# D_OUTPUT.net
KiCad netlist of a schematic drawn in Altium Designer
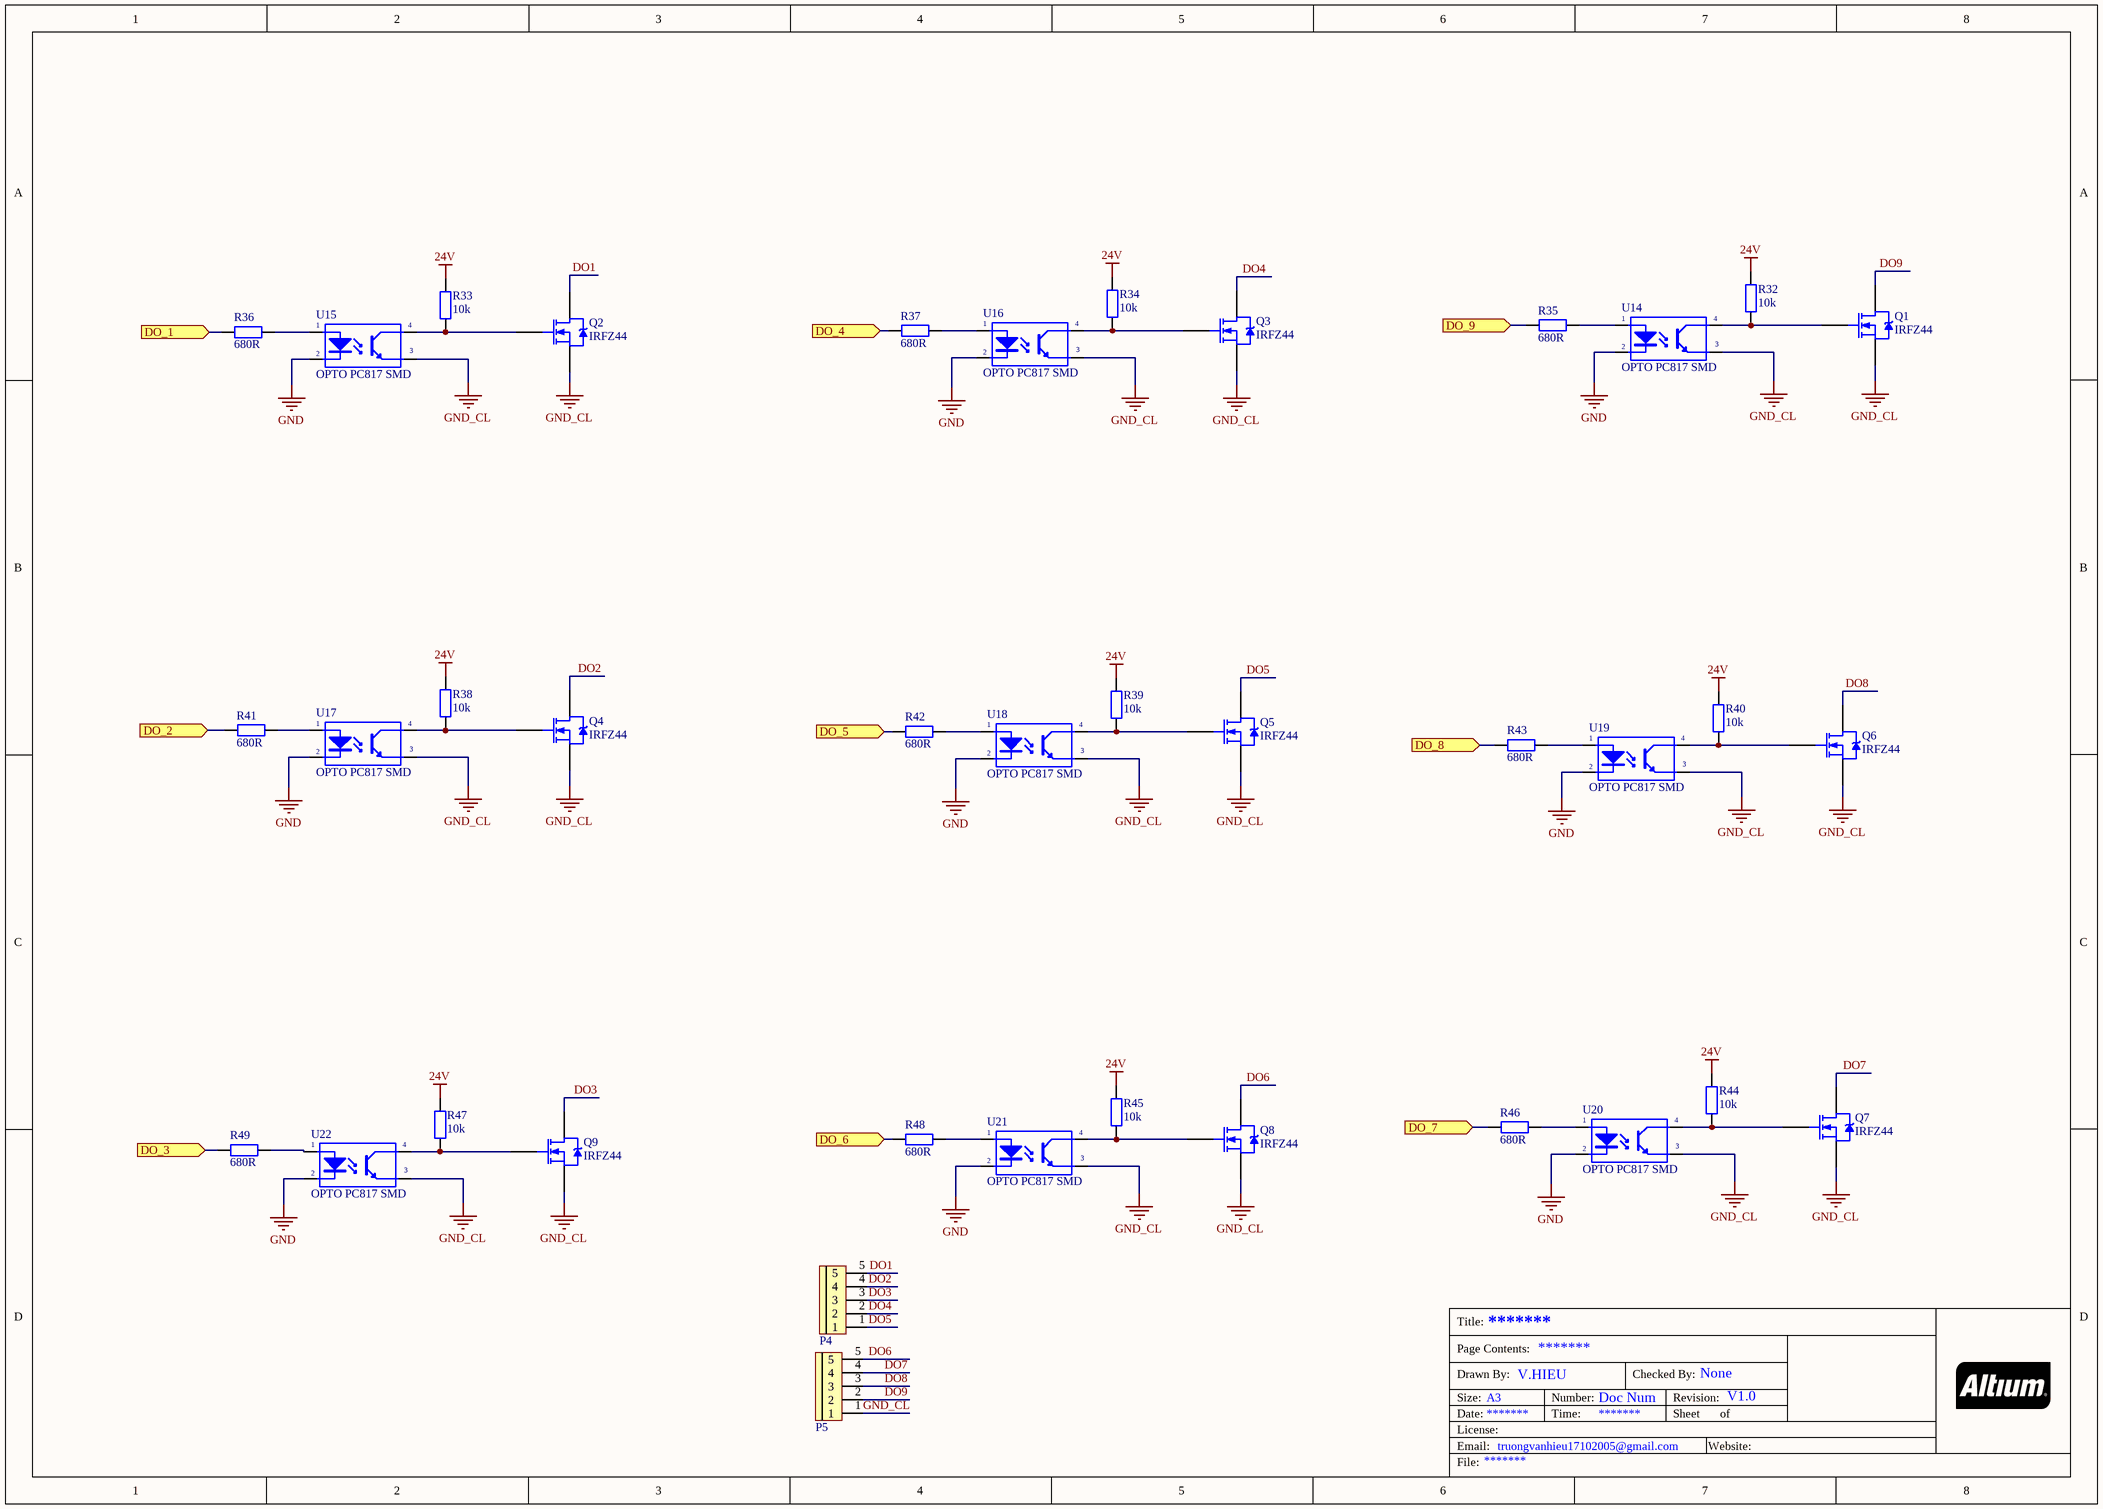
[diagram p0: D_OUTPUT.SchDoc]

(export (version "E")
  (design (tool "Eeschema 10.0.6"))
  (components
    (comp (ref "P4")
      (value "CON 5 EDG5.08")
      (footprint "CON 5 5EDG5.08")
      (description "Cắm")
      (libsource (lib "Altium_Lib_by_KhueNguyenCreator") (part "CON 5 EDG5.08"))
    )
    (comp (ref "P5")
      (value "CON 5 EDG5.08")
      (footprint "CON 5 5EDG5.08")
      (description "Cắm")
      (libsource (lib "Altium_Lib_by_KhueNguyenCreator") (part "CON 5 EDG5.08"))
    )
    (comp (ref "Q1")
      (value "IRFZ44")
      (footprint "TO220")
      (description "TO-220")
      (libsource (lib "Altium_Lib_by_KhueNguyenCreator") (part "FET IRFZ44 DIP"))
    )
    (comp (ref "Q2")
      (value "IRFZ44")
      (footprint "TO220")
      (description "TO-220")
      (libsource (lib "Altium_Lib_by_KhueNguyenCreator") (part "FET IRFZ44 DIP"))
    )
    (comp (ref "Q3")
      (value "IRFZ44")
      (footprint "TO220")
      (description "TO-220")
      (libsource (lib "Altium_Lib_by_KhueNguyenCreator") (part "FET IRFZ44 DIP"))
    )
    (comp (ref "Q4")
      (value "IRFZ44")
      (footprint "TO220")
      (description "TO-220")
      (libsource (lib "Altium_Lib_by_KhueNguyenCreator") (part "FET IRFZ44 DIP"))
    )
    (comp (ref "Q5")
      (value "IRFZ44")
      (footprint "TO220")
      (description "TO-220")
      (libsource (lib "Altium_Lib_by_KhueNguyenCreator") (part "FET IRFZ44 DIP"))
    )
    (comp (ref "Q6")
      (value "IRFZ44")
      (footprint "TO220")
      (description "TO-220")
      (libsource (lib "Altium_Lib_by_KhueNguyenCreator") (part "FET IRFZ44 DIP"))
    )
    (comp (ref "Q7")
      (value "IRFZ44")
      (footprint "TO220")
      (description "TO-220")
      (libsource (lib "Altium_Lib_by_KhueNguyenCreator") (part "FET IRFZ44 DIP"))
    )
    (comp (ref "Q8")
      (value "IRFZ44")
      (footprint "TO220")
      (description "TO-220")
      (libsource (lib "Altium_Lib_by_KhueNguyenCreator") (part "FET IRFZ44 DIP"))
    )
    (comp (ref "Q9")
      (value "IRFZ44")
      (footprint "TO220")
      (description "TO-220")
      (libsource (lib "Altium_Lib_by_KhueNguyenCreator") (part "FET IRFZ44 DIP"))
    )
    (comp (ref "R32")
      (value "10k")
      (footprint "tro smd 0805")
      (description "Dán")
      (libsource (lib "Altium_Lib_by_KhueNguyenCreator") (part "Tro 0805 1% 10k"))
    )
    (comp (ref "R33")
      (value "10k")
      (footprint "tro smd 0805")
      (description "Dán")
      (libsource (lib "Altium_Lib_by_KhueNguyenCreator") (part "Tro 0805 1% 10k"))
    )
    (comp (ref "R34")
      (value "10k")
      (footprint "tro smd 0805")
      (description "Dán")
      (libsource (lib "Altium_Lib_by_KhueNguyenCreator") (part "Tro 0805 1% 10k"))
    )
    (comp (ref "R35")
      (value "680R")
      (footprint "Tro SMD 0805")
      (description "Dán")
      (libsource (lib "Altium_Lib_by_KhueNguyenCreator") (part "Tro 0805 5% 680R"))
    )
    (comp (ref "R36")
      (value "680R")
      (footprint "Tro SMD 0805")
      (description "Dán")
      (libsource (lib "Altium_Lib_by_KhueNguyenCreator") (part "Tro 0805 5% 680R"))
    )
    (comp (ref "R37")
      (value "680R")
      (footprint "Tro SMD 0805")
      (description "Dán")
      (libsource (lib "Altium_Lib_by_KhueNguyenCreator") (part "Tro 0805 5% 680R"))
    )
    (comp (ref "R38")
      (value "10k")
      (footprint "tro smd 0805")
      (description "Dán")
      (libsource (lib "Altium_Lib_by_KhueNguyenCreator") (part "Tro 0805 1% 10k"))
    )
    (comp (ref "R39")
      (value "10k")
      (footprint "tro smd 0805")
      (description "Dán")
      (libsource (lib "Altium_Lib_by_KhueNguyenCreator") (part "Tro 0805 1% 10k"))
    )
    (comp (ref "R40")
      (value "10k")
      (footprint "tro smd 0805")
      (description "Dán")
      (libsource (lib "Altium_Lib_by_KhueNguyenCreator") (part "Tro 0805 1% 10k"))
    )
    (comp (ref "R41")
      (value "680R")
      (footprint "Tro SMD 0805")
      (description "Dán")
      (libsource (lib "Altium_Lib_by_KhueNguyenCreator") (part "Tro 0805 5% 680R"))
    )
    (comp (ref "R42")
      (value "680R")
      (footprint "Tro SMD 0805")
      (description "Dán")
      (libsource (lib "Altium_Lib_by_KhueNguyenCreator") (part "Tro 0805 5% 680R"))
    )
    (comp (ref "R43")
      (value "680R")
      (footprint "Tro SMD 0805")
      (description "Dán")
      (libsource (lib "Altium_Lib_by_KhueNguyenCreator") (part "Tro 0805 5% 680R"))
    )
    (comp (ref "R44")
      (value "10k")
      (footprint "tro smd 0805")
      (description "Dán")
      (libsource (lib "Altium_Lib_by_KhueNguyenCreator") (part "Tro 0805 1% 10k"))
    )
    (comp (ref "R45")
      (value "10k")
      (footprint "tro smd 0805")
      (description "Dán")
      (libsource (lib "Altium_Lib_by_KhueNguyenCreator") (part "Tro 0805 1% 10k"))
    )
    (comp (ref "R46")
      (value "680R")
      (footprint "Tro SMD 0805")
      (description "Dán")
      (libsource (lib "Altium_Lib_by_KhueNguyenCreator") (part "Tro 0805 5% 680R"))
    )
    (comp (ref "R47")
      (value "10k")
      (footprint "tro smd 0805")
      (description "Dán")
      (libsource (lib "Altium_Lib_by_KhueNguyenCreator") (part "Tro 0805 1% 10k"))
    )
    (comp (ref "R48")
      (value "680R")
      (footprint "Tro SMD 0805")
      (description "Dán")
      (libsource (lib "Altium_Lib_by_KhueNguyenCreator") (part "Tro 0805 5% 680R"))
    )
    (comp (ref "R49")
      (value "680R")
      (footprint "Tro SMD 0805")
      (description "Dán")
      (libsource (lib "Altium_Lib_by_KhueNguyenCreator") (part "Tro 0805 5% 680R"))
    )
    (comp (ref "U14")
      (value "OPTO PC817 SMD")
      (footprint "SOP4")
      (description "Single Opto")
      (libsource (lib "Altium_Lib_by_KhueNguyenCreator") (part "OPTO PC817 SMD"))
    )
    (comp (ref "U15")
      (value "OPTO PC817 SMD")
      (footprint "SOP4")
      (description "Single Opto")
      (libsource (lib "Altium_Lib_by_KhueNguyenCreator") (part "OPTO PC817 SMD"))
    )
    (comp (ref "U16")
      (value "OPTO PC817 SMD")
      (footprint "SOP4")
      (description "Single Opto")
      (libsource (lib "Altium_Lib_by_KhueNguyenCreator") (part "OPTO PC817 SMD"))
    )
    (comp (ref "U17")
      (value "OPTO PC817 SMD")
      (footprint "SOP4")
      (description "Single Opto")
      (libsource (lib "Altium_Lib_by_KhueNguyenCreator") (part "OPTO PC817 SMD"))
    )
    (comp (ref "U18")
      (value "OPTO PC817 SMD")
      (footprint "SOP4")
      (description "Single Opto")
      (libsource (lib "Altium_Lib_by_KhueNguyenCreator") (part "OPTO PC817 SMD"))
    )
    (comp (ref "U19")
      (value "OPTO PC817 SMD")
      (footprint "SOP4")
      (description "Single Opto")
      (libsource (lib "Altium_Lib_by_KhueNguyenCreator") (part "OPTO PC817 SMD"))
    )
    (comp (ref "U20")
      (value "OPTO PC817 SMD")
      (footprint "SOP4")
      (description "Single Opto")
      (libsource (lib "Altium_Lib_by_KhueNguyenCreator") (part "OPTO PC817 SMD"))
    )
    (comp (ref "U21")
      (value "OPTO PC817 SMD")
      (footprint "SOP4")
      (description "Single Opto")
      (libsource (lib "Altium_Lib_by_KhueNguyenCreator") (part "OPTO PC817 SMD"))
    )
    (comp (ref "U22")
      (value "OPTO PC817 SMD")
      (footprint "SOP4")
      (description "Single Opto")
      (libsource (lib "Altium_Lib_by_KhueNguyenCreator") (part "OPTO PC817 SMD"))
    )
  )
  (nets
    (net (code "1") (name "/DO1") (class "Default")
      (node (ref "P4") (pin "5") (pinfunction "5_5") (pintype "passive"))
      (node (ref "Q2") (pin "2") (pinfunction "D_2") (pintype "passive"))
    )
    (net (code "2") (name "/DO2") (class "Default")
      (node (ref "P4") (pin "4") (pinfunction "4_4") (pintype "passive"))
      (node (ref "Q4") (pin "2") (pinfunction "D_2") (pintype "passive"))
    )
    (net (code "3") (name "/DO3") (class "Default")
      (node (ref "P4") (pin "3") (pinfunction "3_3") (pintype "passive"))
      (node (ref "Q9") (pin "2") (pinfunction "D_2") (pintype "passive"))
    )
    (net (code "4") (name "/DO4") (class "Default")
      (node (ref "P4") (pin "2") (pinfunction "2_2") (pintype "passive"))
      (node (ref "Q3") (pin "2") (pinfunction "D_2") (pintype "passive"))
    )
    (net (code "5") (name "/DO5") (class "Default")
      (node (ref "P4") (pin "1") (pinfunction "1_1") (pintype "passive"))
      (node (ref "Q5") (pin "2") (pinfunction "D_2") (pintype "passive"))
    )
    (net (code "6") (name "/DO6") (class "Default")
      (node (ref "P5") (pin "5") (pinfunction "5_5") (pintype "passive"))
      (node (ref "Q8") (pin "2") (pinfunction "D_2") (pintype "passive"))
    )
    (net (code "7") (name "/DO7") (class "Default")
      (node (ref "P5") (pin "4") (pinfunction "4_4") (pintype "passive"))
      (node (ref "Q7") (pin "2") (pinfunction "D_2") (pintype "passive"))
    )
    (net (code "8") (name "/DO8") (class "Default")
      (node (ref "P5") (pin "3") (pinfunction "3_3") (pintype "passive"))
      (node (ref "Q6") (pin "2") (pinfunction "D_2") (pintype "passive"))
    )
    (net (code "9") (name "/DO9") (class "Default")
      (node (ref "P5") (pin "2") (pinfunction "2_2") (pintype "passive"))
      (node (ref "Q1") (pin "2") (pinfunction "D_2") (pintype "passive"))
    )
    (net (code "10") (name "/DO_1") (class "Default")
      (node (ref "R36") (pin "1") (pinfunction "1_1") (pintype "passive"))
    )
    (net (code "11") (name "/DO_2") (class "Default")
      (node (ref "R41") (pin "1") (pinfunction "1_1") (pintype "passive"))
    )
    (net (code "12") (name "/DO_3") (class "Default")
      (node (ref "R49") (pin "1") (pinfunction "1_1") (pintype "passive"))
    )
    (net (code "13") (name "/DO_4") (class "Default")
      (node (ref "R37") (pin "1") (pinfunction "1_1") (pintype "passive"))
    )
    (net (code "14") (name "/DO_5") (class "Default")
      (node (ref "R42") (pin "1") (pinfunction "1_1") (pintype "passive"))
    )
    (net (code "15") (name "/DO_6") (class "Default")
      (node (ref "R48") (pin "1") (pinfunction "1_1") (pintype "passive"))
    )
    (net (code "16") (name "/DO_7") (class "Default")
      (node (ref "R46") (pin "1") (pinfunction "1_1") (pintype "passive"))
    )
    (net (code "17") (name "/DO_8") (class "Default")
      (node (ref "R43") (pin "1") (pinfunction "1_1") (pintype "passive"))
    )
    (net (code "18") (name "/DO_9") (class "Default")
      (node (ref "R35") (pin "1") (pinfunction "1_1") (pintype "passive"))
    )
    (net (code "19") (name "24V") (class "Default")
      (node (ref "R32") (pin "1") (pinfunction "1_1") (pintype "passive"))
      (node (ref "R33") (pin "1") (pinfunction "1_1") (pintype "passive"))
      (node (ref "R34") (pin "1") (pinfunction "1_1") (pintype "passive"))
      (node (ref "R38") (pin "1") (pinfunction "1_1") (pintype "passive"))
      (node (ref "R39") (pin "1") (pinfunction "1_1") (pintype "passive"))
      (node (ref "R40") (pin "1") (pinfunction "1_1") (pintype "passive"))
      (node (ref "R44") (pin "1") (pinfunction "1_1") (pintype "passive"))
      (node (ref "R45") (pin "1") (pinfunction "1_1") (pintype "passive"))
      (node (ref "R47") (pin "1") (pinfunction "1_1") (pintype "passive"))
    )
    (net (code "20") (name "GND") (class "Default")
      (node (ref "U14") (pin "2") (pinfunction "K_2") (pintype "passive"))
      (node (ref "U15") (pin "2") (pinfunction "K_2") (pintype "passive"))
      (node (ref "U16") (pin "2") (pinfunction "K_2") (pintype "passive"))
      (node (ref "U17") (pin "2") (pinfunction "K_2") (pintype "passive"))
      (node (ref "U18") (pin "2") (pinfunction "K_2") (pintype "passive"))
      (node (ref "U19") (pin "2") (pinfunction "K_2") (pintype "passive"))
      (node (ref "U20") (pin "2") (pinfunction "K_2") (pintype "passive"))
      (node (ref "U21") (pin "2") (pinfunction "K_2") (pintype "passive"))
      (node (ref "U22") (pin "2") (pinfunction "K_2") (pintype "passive"))
    )
    (net (code "21") (name "GND_CL") (class "Default")
      (node (ref "P5") (pin "1") (pinfunction "1_1") (pintype "passive"))
      (node (ref "Q1") (pin "3") (pinfunction "S_3") (pintype "passive"))
      (node (ref "Q2") (pin "3") (pinfunction "S_3") (pintype "passive"))
      (node (ref "Q3") (pin "3") (pinfunction "S_3") (pintype "passive"))
      (node (ref "Q4") (pin "3") (pinfunction "S_3") (pintype "passive"))
      (node (ref "Q5") (pin "3") (pinfunction "S_3") (pintype "passive"))
      (node (ref "Q6") (pin "3") (pinfunction "S_3") (pintype "passive"))
      (node (ref "Q7") (pin "3") (pinfunction "S_3") (pintype "passive"))
      (node (ref "Q8") (pin "3") (pinfunction "S_3") (pintype "passive"))
      (node (ref "Q9") (pin "3") (pinfunction "S_3") (pintype "passive"))
      (node (ref "U14") (pin "3") (pinfunction "E_3") (pintype "passive"))
      (node (ref "U15") (pin "3") (pinfunction "E_3") (pintype "passive"))
      (node (ref "U16") (pin "3") (pinfunction "E_3") (pintype "passive"))
      (node (ref "U17") (pin "3") (pinfunction "E_3") (pintype "passive"))
      (node (ref "U18") (pin "3") (pinfunction "E_3") (pintype "passive"))
      (node (ref "U19") (pin "3") (pinfunction "E_3") (pintype "passive"))
      (node (ref "U20") (pin "3") (pinfunction "E_3") (pintype "passive"))
      (node (ref "U21") (pin "3") (pinfunction "E_3") (pintype "passive"))
      (node (ref "U22") (pin "3") (pinfunction "E_3") (pintype "passive"))
    )
    (net (code "22") (name "Net-(Q1-G)") (class "Default")
      (node (ref "Q1") (pin "1") (pinfunction "G_1") (pintype "passive"))
      (node (ref "R32") (pin "2") (pinfunction "2_2") (pintype "passive"))
      (node (ref "U14") (pin "4") (pinfunction "C_4") (pintype "passive"))
    )
    (net (code "23") (name "Net-(Q2-G)") (class "Default")
      (node (ref "Q2") (pin "1") (pinfunction "G_1") (pintype "passive"))
      (node (ref "R33") (pin "2") (pinfunction "2_2") (pintype "passive"))
      (node (ref "U15") (pin "4") (pinfunction "C_4") (pintype "passive"))
    )
    (net (code "24") (name "Net-(Q3-G)") (class "Default")
      (node (ref "Q3") (pin "1") (pinfunction "G_1") (pintype "passive"))
      (node (ref "R34") (pin "2") (pinfunction "2_2") (pintype "passive"))
      (node (ref "U16") (pin "4") (pinfunction "C_4") (pintype "passive"))
    )
    (net (code "25") (name "Net-(Q4-G)") (class "Default")
      (node (ref "Q4") (pin "1") (pinfunction "G_1") (pintype "passive"))
      (node (ref "R38") (pin "2") (pinfunction "2_2") (pintype "passive"))
      (node (ref "U17") (pin "4") (pinfunction "C_4") (pintype "passive"))
    )
    (net (code "26") (name "Net-(Q5-G)") (class "Default")
      (node (ref "Q5") (pin "1") (pinfunction "G_1") (pintype "passive"))
      (node (ref "R39") (pin "2") (pinfunction "2_2") (pintype "passive"))
      (node (ref "U18") (pin "4") (pinfunction "C_4") (pintype "passive"))
    )
    (net (code "27") (name "Net-(Q6-G)") (class "Default")
      (node (ref "Q6") (pin "1") (pinfunction "G_1") (pintype "passive"))
      (node (ref "R40") (pin "2") (pinfunction "2_2") (pintype "passive"))
      (node (ref "U19") (pin "4") (pinfunction "C_4") (pintype "passive"))
    )
    (net (code "28") (name "Net-(Q7-G)") (class "Default")
      (node (ref "Q7") (pin "1") (pinfunction "G_1") (pintype "passive"))
      (node (ref "R44") (pin "2") (pinfunction "2_2") (pintype "passive"))
      (node (ref "U20") (pin "4") (pinfunction "C_4") (pintype "passive"))
    )
    (net (code "29") (name "Net-(Q8-G)") (class "Default")
      (node (ref "Q8") (pin "1") (pinfunction "G_1") (pintype "passive"))
      (node (ref "R45") (pin "2") (pinfunction "2_2") (pintype "passive"))
      (node (ref "U21") (pin "4") (pinfunction "C_4") (pintype "passive"))
    )
    (net (code "30") (name "Net-(Q9-G)") (class "Default")
      (node (ref "Q9") (pin "1") (pinfunction "G_1") (pintype "passive"))
      (node (ref "R47") (pin "2") (pinfunction "2_2") (pintype "passive"))
      (node (ref "U22") (pin "4") (pinfunction "C_4") (pintype "passive"))
    )
    (net (code "31") (name "Net-(U14-A)") (class "Default")
      (node (ref "R35") (pin "2") (pinfunction "2_2") (pintype "passive"))
      (node (ref "U14") (pin "1") (pinfunction "A_1") (pintype "passive"))
    )
    (net (code "32") (name "Net-(U15-A)") (class "Default")
      (node (ref "R36") (pin "2") (pinfunction "2_2") (pintype "passive"))
      (node (ref "U15") (pin "1") (pinfunction "A_1") (pintype "passive"))
    )
    (net (code "33") (name "Net-(U16-A)") (class "Default")
      (node (ref "R37") (pin "2") (pinfunction "2_2") (pintype "passive"))
      (node (ref "U16") (pin "1") (pinfunction "A_1") (pintype "passive"))
    )
    (net (code "34") (name "Net-(U17-A)") (class "Default")
      (node (ref "R41") (pin "2") (pinfunction "2_2") (pintype "passive"))
      (node (ref "U17") (pin "1") (pinfunction "A_1") (pintype "passive"))
    )
    (net (code "35") (name "Net-(U18-A)") (class "Default")
      (node (ref "R42") (pin "2") (pinfunction "2_2") (pintype "passive"))
      (node (ref "U18") (pin "1") (pinfunction "A_1") (pintype "passive"))
    )
    (net (code "36") (name "Net-(U19-A)") (class "Default")
      (node (ref "R43") (pin "2") (pinfunction "2_2") (pintype "passive"))
      (node (ref "U19") (pin "1") (pinfunction "A_1") (pintype "passive"))
    )
    (net (code "37") (name "Net-(U20-A)") (class "Default")
      (node (ref "R46") (pin "2") (pinfunction "2_2") (pintype "passive"))
      (node (ref "U20") (pin "1") (pinfunction "A_1") (pintype "passive"))
    )
    (net (code "38") (name "Net-(U21-A)") (class "Default")
      (node (ref "R48") (pin "2") (pinfunction "2_2") (pintype "passive"))
      (node (ref "U21") (pin "1") (pinfunction "A_1") (pintype "passive"))
    )
    (net (code "39") (name "Net-(U22-A)") (class "Default")
      (node (ref "R49") (pin "2") (pinfunction "2_2") (pintype "passive"))
      (node (ref "U22") (pin "1") (pinfunction "A_1") (pintype "passive"))
    )
  )
)
